# transmitter.net
KiCad netlist of a schematic drawn in Altium Designer
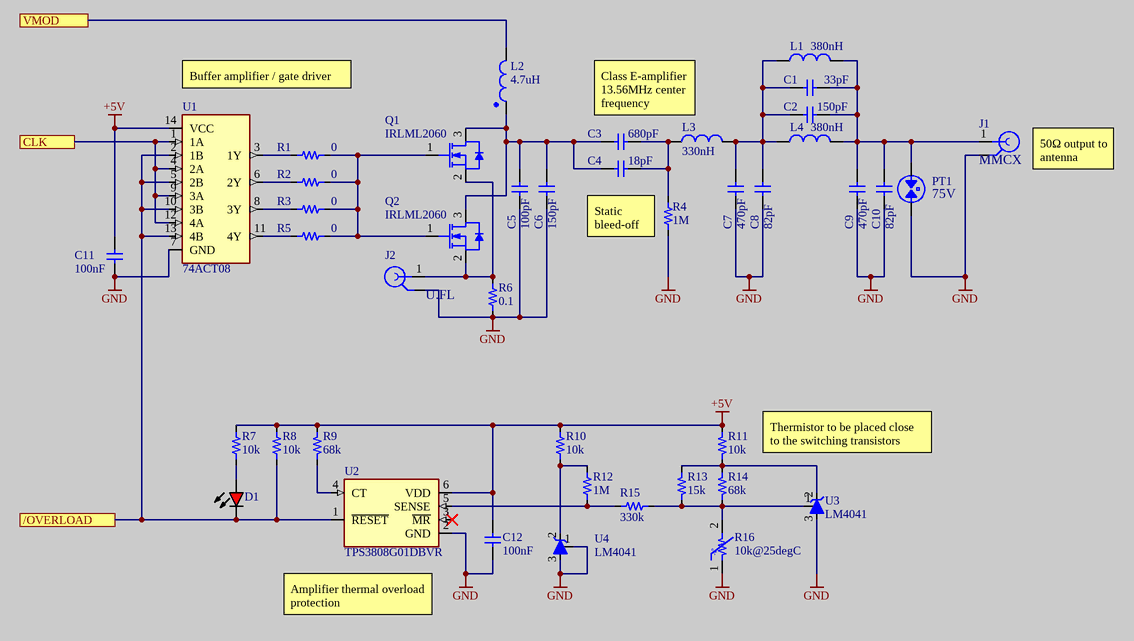
[diagram p0: transmitter.SchDoc]

(export (version "E")
  (design (tool "Eeschema 10.0.6"))
  (components
    (comp (ref "C1")
      (value "33pF")
      (footprint "1206-C-L")
      (description "WCAP-CSGP Multilayer Ceramic Chip Capacitor, General Purpose, size 1206, NP0, 33pF, 50VDC")
      (fields (field (name "TOLERANCE") "5%") (field (name "JLCPCB PART #") "C571053"))
      (libsource (lib "7c7 Engineering") (part "CAP-NP-2"))
    )
    (comp (ref "C2")
      (value "150pF")
      (footprint "1206-C-N")
      (description "WCAP-CSGP Multilayer Ceramic Chip Capacitor, General Purpose, size 1206, NP0, 150pF, 100VDC")
      (fields (field (name "TOLERANCE") "5%") (field (name "JLCPCB PART #") "C162445"))
      (libsource (lib "7c7 Engineering") (part "CAP-NP-2"))
    )
    (comp (ref "C3")
      (value "680pF")
      (footprint "1206-C-L")
      (description "WCAP-CSGP Multilayer Ceramic Chip Capacitor, General Purpose, size 1206, NP0, 680pF, 100VDC")
      (fields (field (name "TOLERANCE") "5%") (field (name "JLCPCB PART #") "C541497"))
      (libsource (lib "7c7 Engineering") (part "CAP-NP-2"))
    )
    (comp (ref "C4")
      (value "18pF")
      (footprint "1206-C-N")
      (description "Surface Mount Ceramic Multilayer Capacitor 18pF 5% C0G 1kV 1206 Blister T/R")
      (fields (field (name "TOLERANCE") "5%") (field (name "JLCPCB PART #") "C33039"))
      (libsource (lib "7c7 Engineering") (part "CAP-NP-2"))
    )
    (comp (ref "C5")
      (value "100pF")
      (footprint "1206-C-N")
      (fields
        (field (name "JLCPCB PART #") "C9188")
        (field (name "TOLERANCE") "5%")
        (field (name "Comment") "Capacitor 100pF +/-5% 630V NP0 Class I 1206")
      )
      (libsource (lib "7c7 Engineering") (part "CAP-NP-2"))
    )
    (comp (ref "C6")
      (value "150pF")
      (footprint "1206-C-N")
      (description "WCAP-CSGP Multilayer Ceramic Chip Capacitor, General Purpose, size 1206, NP0, 150pF, 100VDC")
      (fields (field (name "TOLERANCE") "5%") (field (name "JLCPCB PART #") "C162445"))
      (libsource (lib "7c7 Engineering") (part "CAP-NP-2"))
    )
    (comp (ref "C7")
      (value "470pF")
      (footprint "1206-C-L")
      (description "WCAP-CSGP Multilayer Ceramic Chip Capacitor, General Purpose, size 1206, NP0, 470pF, 100VDC")
      (fields (field (name "TOLERANCE") "5%") (field (name "JLCPCB PART #") "C107177"))
      (libsource (lib "7c7 Engineering") (part "CAP-NP-2"))
    )
    (comp (ref "C8")
      (value "82pF")
      (footprint "1206-C-N")
      (description "Cap Ceramic 82pF 1000V C0G 5% Pad SMD 1206 125C T/R")
      (fields (field (name "JLCPCB PART #") "C396810") (field (name "Comment") "1206N820J102CT"))
      (libsource (lib "7c7 Engineering") (part "CAP-NP-2"))
    )
    (comp (ref "C9")
      (value "470pF")
      (footprint "1206-C-L")
      (description "WCAP-CSGP Multilayer Ceramic Chip Capacitor, General Purpose, size 1206, NP0, 470pF, 100VDC")
      (fields (field (name "TOLERANCE") "5%") (field (name "JLCPCB PART #") "C107177"))
      (libsource (lib "7c7 Engineering") (part "CAP-NP-2"))
    )
    (comp (ref "C10")
      (value "82pF")
      (footprint "1206-C-N")
      (description "Cap Ceramic 82pF 1000V C0G 5% Pad SMD 1206 125C T/R")
      (fields (field (name "JLCPCB PART #") "C396810") (field (name "Comment") "1206N820J102CT"))
      (libsource (lib "7c7 Engineering") (part "CAP-NP-2"))
    )
    (comp (ref "C11")
      (value "100nF")
      (footprint "0603-C-N")
      (description "WCAP-CSGP Multilayer Ceramic Chip Capacitor, General Purpose, size 0603, X7R, 100nF, 50VDC")
      (fields (field (name "TOLERANCE") "10%") (field (name "JLCPCB PART #") "C14663"))
      (libsource (lib "7c7 Engineering") (part "CAP-NP-2"))
    )
    (comp (ref "C12")
      (value "100nF")
      (footprint "0603-C-N")
      (description "WCAP-CSGP Multilayer Ceramic Chip Capacitor, General Purpose, size 0603, X7R, 100nF, 50VDC")
      (fields (field (name "TOLERANCE") "10%") (field (name "JLCPCB PART #") "C14663"))
      (libsource (lib "7c7 Engineering") (part "CAP-NP-2"))
    )
    (comp (ref "D1")
      (value "150060RS86000")
      (footprint "WL-SMCW_0603_150060xx8x000")
      (description "WL-SMCW Mono-color Chip LED Waterclear, size 0603, Red, 2V, 60°")
      (fields (field (name "JLCPCB PART #") "C5875741") (field (name "MANUFACTURER") "Wurth Elektronik"))
      (libsource (lib "7c7 Engineering") (part "LED-RED-2"))
    )
    (comp (ref "J1")
      (value "66011002111501")
      (footprint "66011002111501")
      (description "WR-MMCX PCB Jack, THT, Right Angle, 6GHz, 50O")
      (fields (field (name "JLCPCB PART #") "C2894793") (field (name "MANUFACTURER") "Wurth Elektronik"))
      (libsource (lib "7c7 Engineering") (part "CN_COAX"))
    )
    (comp (ref "J2")
      (value "U.FL-R-SMT(10)")
      (footprint "HRS-U.FL-R-SMT_V")
      (fields (field (name "JLCPCB PART #") "C88373") (field (name "MANUFACTURER") "Hirose Electric"))
      (libsource (lib "") (part "CN_COAX_1"))
    )
    (comp (ref "L1")
      (value "744918238")
      (footprint "WE-CAIR_5910")
      (description "WE-CAIR SMT Air Coil, size 5910, 380nH, 2.5A, 50mO")
      (fields (field (name "MANUFACTURER") "Wurth Elektronik") (field (name "INDUCTANCE") "380nH"))
      (libsource (lib "7c7 Engineering") (part "IND"))
    )
    (comp (ref "L2")
      (value "784771047")
      (footprint "WE-PDA_1260")
      (description "WE-PDA SMT Shielded Power Inductor, size 1260, 4.7uH, 6.2A, 17.5mOhm")
      (fields (field (name "MANUFACTURER") "Wurth Elektronik") (field (name "INDUCTANCE") "4.7uH"))
      (libsource (lib "7c7 Engineering") (part "IND_POLAR-2"))
    )
    (comp (ref "L3")
      (value "330nH")
      (footprint "IND_2929SQ-331")
      (description "RF inductor, air core, 2% tol, SMT, RoHS, halogen-free")
      (fields (field (name "TOLERANCE") "2%") (field (name "JLCPCB PART #") "C20623511"))
      (libsource (lib "7c7 Engineering") (part "IND"))
    )
    (comp (ref "L4")
      (value "744918238")
      (footprint "WE-CAIR_5910")
      (description "WE-CAIR SMT Air Coil, size 5910, 380nH, 2.5A, 50mO")
      (fields (field (name "MANUFACTURER") "Wurth Elektronik") (field (name "INDUCTANCE") "380nH"))
      (libsource (lib "7c7 Engineering") (part "IND"))
    )
    (comp (ref "PT1")
      (value "GTCC23-750M-R01-2")
      (footprint "GDT_4532")
      (description "Gas Discharge Tubes - GDTs / Gas Plasma Arrestors 75VDC 2-POLE 600V @1KV/US")
      (fields (field (name "JLCPCB PART #") "C9234") (field (name "TOLERANCE") "20%"))
      (libsource (lib "7c7 Engineering") (part "PT_GDT"))
    )
    (comp (ref "Q1")
      (value "IRLML2060")
      (footprint "SOT-23-3-N")
      (description "60V Single N-Channel HEXFET Power MOSFET in a Micro 3 package, SOT23-3, RoHS")
      (fields (field (name "JLCPCB PART #") "C67275") (field (name "Comment") "IRLML2060TRPBF"))
      (libsource (lib "7c7 Engineering") (part "NEMOS-GSD-3"))
    )
    (comp (ref "Q2")
      (value "IRLML2060")
      (footprint "SOT-23-3-N")
      (description "60V Single N-Channel HEXFET Power MOSFET in a Micro 3 package, SOT23-3, RoHS")
      (fields (field (name "JLCPCB PART #") "C67275") (field (name "Comment") "IRLML2060TRPBF"))
      (libsource (lib "7c7 Engineering") (part "NEMOS-GSD-3"))
    )
    (comp (ref "R1")
      (value "0")
      (footprint "0603-R-N")
      (description "Chip Jumper, Thick Film, Jumper, 0603, 100mW, 1A, 0 Ohm, <50 mOhm")
      (fields (field (name "FLIR PART #") "YRES0E-1") (field (name "TOLERANCE") "50 mOhm"))
      (libsource (lib "7c7 Engineering") (part "RES"))
    )
    (comp (ref "R2")
      (value "0")
      (footprint "0603-R-N")
      (description "Chip Jumper, Thick Film, Jumper, 0603, 100mW, 1A, 0 Ohm, <50 mOhm")
      (fields (field (name "FLIR PART #") "YRES0E-1") (field (name "TOLERANCE") "50 mOhm"))
      (libsource (lib "7c7 Engineering") (part "RES"))
    )
    (comp (ref "R3")
      (value "0")
      (footprint "0603-R-N")
      (description "Chip Jumper, Thick Film, Jumper, 0603, 100mW, 1A, 0 Ohm, <50 mOhm")
      (fields (field (name "FLIR PART #") "YRES0E-1") (field (name "TOLERANCE") "50 mOhm"))
      (libsource (lib "7c7 Engineering") (part "RES"))
    )
    (comp (ref "R4")
      (value "1M")
      (footprint "1206-R-N")
      (description "Res Thick Film 1206 1M Ohm 1% 0.25W(1/4W) ±100ppm/C SMD T/R")
      (fields (field (name "JLCPCB PART #") "C17927") (field (name "TOLERANCE") "1%"))
      (libsource (lib "7c7 Engineering") (part "RES"))
    )
    (comp (ref "R5")
      (value "0")
      (footprint "0603-R-N")
      (description "Chip Jumper, Thick Film, Jumper, 0603, 100mW, 1A, 0 Ohm, <50 mOhm")
      (fields (field (name "FLIR PART #") "YRES0E-1") (field (name "TOLERANCE") "50 mOhm"))
      (libsource (lib "7c7 Engineering") (part "RES"))
    )
    (comp (ref "R6")
      (value "0.1")
      (footprint "1206-R-N")
      (description "Res Thick Film 1206 0.1 Ohm 1% 1/2W ±100ppm/°C Molded SMD SMD Paper T/R")
      (fields (field (name "JLCPCB PART #") "C346763") (field (name "TOLERANCE") "1%"))
      (libsource (lib "7c7 Engineering") (part "RES"))
    )
    (comp (ref "R7")
      (value "10k")
      (footprint "0603-R-N")
      (description "Chip Resistor, Thick Film, General Purpose, 0603, 100mW, 50V, 10 kOhm, +/-1%")
      (fields (field (name "JLCPCB PART #") "C25804") (field (name "FLIR PART #") "YRES10K-1"))
      (libsource (lib "7c7 Engineering") (part "RES"))
    )
    (comp (ref "R8")
      (value "10k")
      (footprint "0603-R-N")
      (description "Chip Resistor, Thick Film, General Purpose, 0603, 100mW, 50V, 10 kOhm, +/-1%")
      (fields (field (name "JLCPCB PART #") "C25804") (field (name "FLIR PART #") "YRES10K-1"))
      (libsource (lib "7c7 Engineering") (part "RES"))
    )
    (comp (ref "R9")
      (value "68k")
      (footprint "0603-R-N")
      (description "Chip Resistor, Thick Film, General Purpose, 0603, 100mW, 50V, 68 kOhm, +/-1%")
      (fields (field (name "TOLERANCE") "1%") (field (name "JLCPCB PART #") "C114633"))
      (libsource (lib "7c7 Engineering") (part "RES"))
    )
    (comp (ref "R10")
      (value "10k")
      (footprint "0603-R-N")
      (description "Chip Resistor, Thick Film, General Purpose, 0603, 100mW, 50V, 10 kOhm, +/-1%")
      (fields (field (name "JLCPCB PART #") "C25804") (field (name "FLIR PART #") "YRES10K-1"))
      (libsource (lib "7c7 Engineering") (part "RES"))
    )
    (comp (ref "R11")
      (value "10k")
      (footprint "0603-R-N")
      (description "Chip Resistor, Thick Film, General Purpose, 0603, 100mW, 50V, 10 kOhm, +/-1%")
      (fields (field (name "JLCPCB PART #") "C25804") (field (name "FLIR PART #") "YRES10K-1"))
      (libsource (lib "7c7 Engineering") (part "RES"))
    )
    (comp (ref "R12")
      (value "1M")
      (footprint "0603-R-N")
      (description "Chip Resistor, Thick Film, General Purpose, 0603, 100mW, 50V, 1 MOhm, +/-1%")
      (fields (field (name "TOLERANCE") "1%") (field (name "JLCPCB PART #") "C22935"))
      (libsource (lib "7c7 Engineering") (part "RES"))
    )
    (comp (ref "R13")
      (value "15k")
      (footprint "0603-R-N")
      (description "Chip Resistor, Thick Film, General Purpose, 0603, 100mW, 50V, 15 kOhm, +/-1%")
      (fields (field (name "JLCPCB PART #") "C22809") (field (name "TOLERANCE") "1%"))
      (libsource (lib "7c7 Engineering") (part "RES"))
    )
    (comp (ref "R14")
      (value "68k")
      (footprint "0603-R-N")
      (description "Chip Resistor, Thick Film, General Purpose, 0603, 100mW, 50V, 68 kOhm, +/-1%")
      (fields (field (name "TOLERANCE") "1%") (field (name "JLCPCB PART #") "C114633"))
      (libsource (lib "7c7 Engineering") (part "RES"))
    )
    (comp (ref "R15")
      (value "330k")
      (footprint "0603-R-N")
      (description "Chip Resistor, Thick Film, General Purpose, 0603, 100mW, 50V, 330 kOhm, +/-1%")
      (fields (field (name "TOLERANCE") "1%") (field (name "JLCPCB PART #") "C23137"))
      (libsource (lib "7c7 Engineering") (part "RES"))
    )
    (comp (ref "R16")
      (value "10k@25degC")
      (footprint "0603-R-N")
      (description "Thermistor NTC 10K Ohm 5% 2-Pin 0603 Surface Mount Solder Pad 3450K T/R")
      (fields (field (name "TOLERANCE") "1%") (field (name "JLCPCB PART #") "C13564"))
      (libsource (lib "7c7 Engineering") (part "RES-NTC"))
    )
    (comp (ref "U1")
      (value "74ACT08")
      (footprint "SOIC14-N")
      (description "And Gate 4-ELEMENT 2-IN Cmos Automotive 14-PIN SOIC N T/r / IC Gate And 4CH 2-INP 14-SOIC")
      (fields (field (name "JLCPCB PART #") "C233452") (field (name "Comment") "MC74ACT08DR2G"))
      (libsource (lib "7c7 Engineering") (part ".Value"))
    )
    (comp (ref "U2")
      (value "TPS3808G01DBVR")
      (footprint "SOT-23-6")
      (description "Supervisor Open Drain or Open Collector 1 Channel SOT-23-6")
      (fields (field (name "JLCPCB PART #") "C19653"))
      (libsource (lib "7c7 Engineering") (part "TPS3808G01DBV6"))
    )
    (comp (ref "U3")
      (value "LM4041")
      (footprint "SOT-23-3-N")
      (description "Fixed & adjustable, 45-µA, precision micropower shunt voltage reference 3-SOT-23 -40 to 85")
      (fields (field (name "JLCPCB PART #") "C2156756") (field (name "TOLERANCE") "1%"))
      (libsource (lib "7c7 Engineering") (part "IC_TLV431"))
    )
    (comp (ref "U4")
      (value "LM4041")
      (footprint "SOT-23-3-N")
      (description "Fixed & adjustable, 45-µA, precision micropower shunt voltage reference 3-SOT-23 -40 to 85")
      (fields (field (name "JLCPCB PART #") "C2156756") (field (name "TOLERANCE") "1%"))
      (libsource (lib "7c7 Engineering") (part "IC_TLV431"))
    )
  )
  (nets
    (net (code "1") (name "+5V") (class "Default")
      (node (ref "C11") (pin "2") (pinfunction "2_2") (pintype "passive"))
      (node (ref "C12") (pin "2") (pinfunction "2_2") (pintype "passive"))
      (node (ref "R10") (pin "2") (pinfunction "2_2") (pintype "passive"))
      (node (ref "R11") (pin "2") (pinfunction "2_2") (pintype "passive"))
      (node (ref "R7") (pin "2") (pinfunction "2_2") (pintype "passive"))
      (node (ref "R8") (pin "2") (pinfunction "2_2") (pintype "passive"))
      (node (ref "R9") (pin "1") (pinfunction "1_1") (pintype "passive"))
      (node (ref "U1") (pin "14") (pinfunction "VCC_14") (pintype "power_in"))
      (node (ref "U2") (pin "6") (pinfunction "VDD_6") (pintype "power_in"))
    )
    (net (code "2") (name "/CLK") (class "Default")
      (node (ref "U1") (pin "1") (pinfunction "1A_1") (pintype "input"))
      (node (ref "U1") (pin "12") (pinfunction "4A_12") (pintype "input"))
      (node (ref "U1") (pin "4") (pinfunction "2A_4") (pintype "input"))
      (node (ref "U1") (pin "9") (pinfunction "3A_9") (pintype "input"))
    )
    (net (code "3") (name "/VMOD") (class "Default")
      (node (ref "L2") (pin "2") (pinfunction "2_2") (pintype "passive"))
    )
    (net (code "4") (name "/{slash}OVERLOAD") (class "Default")
      (node (ref "D1") (pin "1") (pinfunction "K_1") (pintype "passive"))
      (node (ref "R8") (pin "1") (pinfunction "1_1") (pintype "passive"))
      (node (ref "U1") (pin "10") (pinfunction "3B_10") (pintype "input"))
      (node (ref "U1") (pin "13") (pinfunction "4B_13") (pintype "input"))
      (node (ref "U1") (pin "2") (pinfunction "1B_2") (pintype "input"))
      (node (ref "U1") (pin "5") (pinfunction "2B_5") (pintype "input"))
      (node (ref "U2") (pin "1") (pinfunction "~{RESET}_1") (pintype "tri_state"))
    )
    (net (code "5") (name "GND") (class "Default")
      (node (ref "C10") (pin "1") (pinfunction "1_1") (pintype "passive"))
      (node (ref "C11") (pin "1") (pinfunction "1_1") (pintype "passive"))
      (node (ref "C12") (pin "1") (pinfunction "1_1") (pintype "passive"))
      (node (ref "C5") (pin "1") (pinfunction "1_1") (pintype "passive"))
      (node (ref "C6") (pin "1") (pinfunction "1_1") (pintype "passive"))
      (node (ref "C7") (pin "1") (pinfunction "1_1") (pintype "passive"))
      (node (ref "C8") (pin "1") (pinfunction "1_1") (pintype "passive"))
      (node (ref "C9") (pin "1") (pinfunction "1_1") (pintype "passive"))
      (node (ref "J1") (pin "2") (pinfunction "GND_2") (pintype "passive"))
      (node (ref "J2") (pin "2") (pinfunction "GND_2") (pintype "passive"))
      (node (ref "PT1") (pin "2") (pinfunction "2_2") (pintype "passive"))
      (node (ref "R16") (pin "1") (pinfunction "1_1") (pintype "passive"))
      (node (ref "R4") (pin "1") (pinfunction "1_1") (pintype "passive"))
      (node (ref "R6") (pin "2") (pinfunction "2_2") (pintype "passive"))
      (node (ref "U1") (pin "7") (pinfunction "GND_7") (pintype "power_in"))
      (node (ref "U2") (pin "2") (pinfunction "GND_2") (pintype "power_in"))
      (node (ref "U3") (pin "3") (pinfunction "A_3") (pintype "power_in"))
      (node (ref "U4") (pin "1") (pinfunction "rEF_1") (pintype "passive"))
      (node (ref "U4") (pin "3") (pinfunction "A_3") (pintype "power_in"))
    )
    (net (code "6") (name "Net-(C1-Pad1)") (class "Default")
      (node (ref "C1") (pin "1") (pinfunction "1_1") (pintype "passive"))
      (node (ref "C2") (pin "2") (pinfunction "2_2") (pintype "passive"))
      (node (ref "C7") (pin "2") (pinfunction "2_2") (pintype "passive"))
      (node (ref "C8") (pin "2") (pinfunction "2_2") (pintype "passive"))
      (node (ref "L1") (pin "1") (pinfunction "1_1") (pintype "passive"))
      (node (ref "L3") (pin "2") (pinfunction "2_2") (pintype "passive"))
      (node (ref "L4") (pin "1") (pinfunction "1_1") (pintype "passive"))
    )
    (net (code "7") (name "Net-(C3-Pad2)") (class "Default")
      (node (ref "C3") (pin "2") (pinfunction "2_2") (pintype "passive"))
      (node (ref "C4") (pin "2") (pinfunction "2_2") (pintype "passive"))
      (node (ref "L3") (pin "1") (pinfunction "1_1") (pintype "passive"))
      (node (ref "R4") (pin "2") (pinfunction "2_2") (pintype "passive"))
    )
    (net (code "8") (name "Net-(D1-A)") (class "Default")
      (node (ref "D1") (pin "2") (pinfunction "A_2") (pintype "passive"))
      (node (ref "R7") (pin "1") (pinfunction "1_1") (pintype "passive"))
    )
    (net (code "9") (name "Net-(J1-SIG)") (class "Default")
      (node (ref "C1") (pin "2") (pinfunction "2_2") (pintype "passive"))
      (node (ref "C10") (pin "2") (pinfunction "2_2") (pintype "passive"))
      (node (ref "C2") (pin "1") (pinfunction "1_1") (pintype "passive"))
      (node (ref "C9") (pin "2") (pinfunction "2_2") (pintype "passive"))
      (node (ref "J1") (pin "1") (pinfunction "SIG_1") (pintype "passive"))
      (node (ref "L1") (pin "2") (pinfunction "2_2") (pintype "passive"))
      (node (ref "L4") (pin "2") (pinfunction "2_2") (pintype "passive"))
      (node (ref "PT1") (pin "1") (pinfunction "1_1") (pintype "passive"))
    )
    (net (code "10") (name "Net-(J2-SIG)") (class "Default")
      (node (ref "J2") (pin "1") (pinfunction "SIG_1") (pintype "passive"))
      (node (ref "Q1") (pin "2") (pinfunction "S_2") (pintype "passive"))
      (node (ref "Q2") (pin "2") (pinfunction "S_2") (pintype "passive"))
      (node (ref "R6") (pin "1") (pinfunction "1_1") (pintype "passive"))
    )
    (net (code "11") (name "Net-(Q1-D)") (class "Default")
      (node (ref "C3") (pin "1") (pinfunction "1_1") (pintype "passive"))
      (node (ref "C4") (pin "1") (pinfunction "1_1") (pintype "passive"))
      (node (ref "C5") (pin "2") (pinfunction "2_2") (pintype "passive"))
      (node (ref "C6") (pin "2") (pinfunction "2_2") (pintype "passive"))
      (node (ref "L2") (pin "1") (pinfunction "1_1") (pintype "passive"))
      (node (ref "Q1") (pin "3") (pinfunction "D_3") (pintype "passive"))
      (node (ref "Q2") (pin "3") (pinfunction "D_3") (pintype "passive"))
    )
    (net (code "12") (name "Net-(Q1-G)") (class "Default")
      (node (ref "Q1") (pin "1") (pinfunction "G_1") (pintype "passive"))
      (node (ref "Q2") (pin "1") (pinfunction "G_1") (pintype "passive"))
      (node (ref "R1") (pin "2") (pinfunction "2_2") (pintype "passive"))
      (node (ref "R2") (pin "2") (pinfunction "2_2") (pintype "passive"))
      (node (ref "R3") (pin "2") (pinfunction "2_2") (pintype "passive"))
      (node (ref "R5") (pin "2") (pinfunction "2_2") (pintype "passive"))
    )
    (net (code "13") (name "Net-(U1-1Y)") (class "Default")
      (node (ref "R1") (pin "1") (pinfunction "1_1") (pintype "passive"))
      (node (ref "U1") (pin "3") (pinfunction "1Y_3") (pintype "output"))
    )
    (net (code "14") (name "Net-(U1-2Y)") (class "Default")
      (node (ref "R2") (pin "1") (pinfunction "1_1") (pintype "passive"))
      (node (ref "U1") (pin "6") (pinfunction "2Y_6") (pintype "output"))
    )
    (net (code "15") (name "Net-(U1-3Y)") (class "Default")
      (node (ref "R3") (pin "1") (pinfunction "1_1") (pintype "passive"))
      (node (ref "U1") (pin "8") (pinfunction "3Y_8") (pintype "output"))
    )
    (net (code "16") (name "Net-(U1-4Y)") (class "Default")
      (node (ref "R5") (pin "1") (pinfunction "1_1") (pintype "passive"))
      (node (ref "U1") (pin "11") (pinfunction "4Y_11") (pintype "output"))
    )
    (net (code "17") (name "Net-(U2-CT)") (class "Default")
      (node (ref "R9") (pin "2") (pinfunction "2_2") (pintype "passive"))
      (node (ref "U2") (pin "4") (pinfunction "CT_4") (pintype "input"))
    )
    (net (code "18") (name "Net-(U2-SENSE)") (class "Default")
      (node (ref "R12") (pin "1") (pinfunction "1_1") (pintype "passive"))
      (node (ref "R15") (pin "1") (pinfunction "1_1") (pintype "passive"))
      (node (ref "U2") (pin "5") (pinfunction "SENSE_5") (pintype "input"))
    )
    (net (code "19") (name "Net-(U3-C)") (class "Default")
      (node (ref "R11") (pin "1") (pinfunction "1_1") (pintype "passive"))
      (node (ref "R13") (pin "2") (pinfunction "2_2") (pintype "passive"))
      (node (ref "R14") (pin "2") (pinfunction "2_2") (pintype "passive"))
      (node (ref "U3") (pin "2") (pinfunction "C_2") (pintype "power_in"))
    )
    (net (code "20") (name "Net-(U3-rEF)") (class "Default")
      (node (ref "R13") (pin "1") (pinfunction "1_1") (pintype "passive"))
      (node (ref "R14") (pin "1") (pinfunction "1_1") (pintype "passive"))
      (node (ref "R15") (pin "2") (pinfunction "2_2") (pintype "passive"))
      (node (ref "R16") (pin "2") (pinfunction "2_2") (pintype "passive"))
      (node (ref "U3") (pin "1") (pinfunction "rEF_1") (pintype "passive"))
    )
    (net (code "21") (name "Net-(U4-C)") (class "Default")
      (node (ref "R10") (pin "1") (pinfunction "1_1") (pintype "passive"))
      (node (ref "R12") (pin "2") (pinfunction "2_2") (pintype "passive"))
      (node (ref "U4") (pin "2") (pinfunction "C_2") (pintype "power_in"))
    )
    (net (code "22") (name "unconnected-(U2-~{MR}-Pad3)") (class "Default")
      (node (ref "U2") (pin "3") (pinfunction "~{MR}_3") (pintype "input+no_connect"))
    )
  )
)
